# 8860.net
KiCad netlist of a schematic drawn in Altium Designer
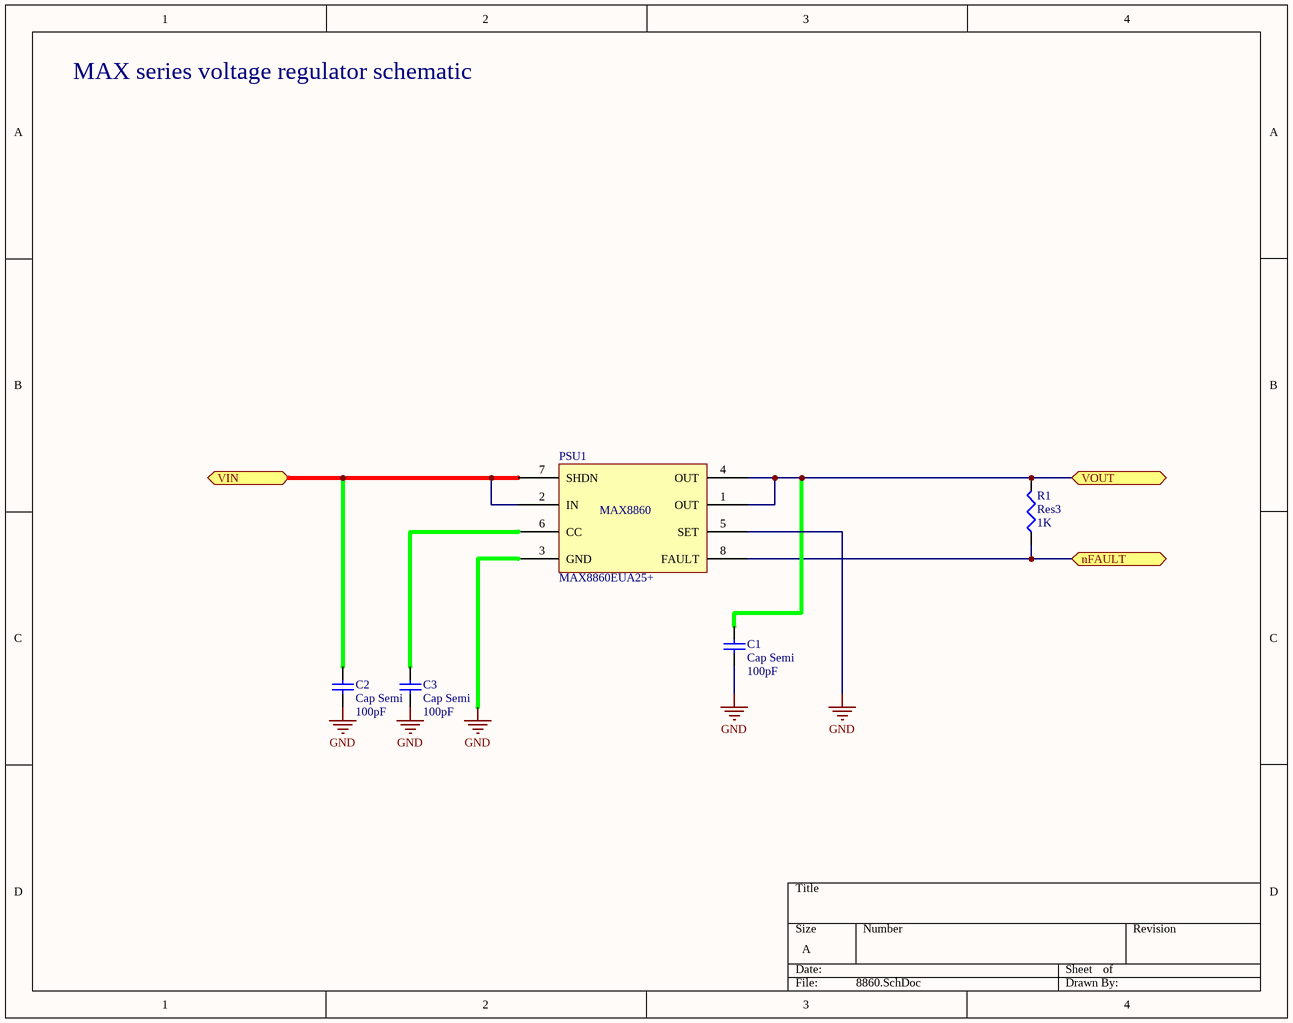
[diagram p0: 8860.SchDoc]

(export (version "E")
  (design (tool "Eeschema 10.0.6"))
  (components
    (comp (ref "C1")
      (value "Cap Semi")
      (footprint "C1206")
      (description "Capacitor (Semiconductor SIM Model)")
      (fields (field (name "ALTIUM_VALUE") "100pF") (field (name "PUBLISHER") "Altium Limited"))
      (libsource (lib "Miscellaneous Devices") (part "Cap Semi"))
    )
    (comp (ref "C2")
      (value "Cap Semi")
      (footprint "C1206")
      (description "Capacitor (Semiconductor SIM Model)")
      (fields (field (name "ALTIUM_VALUE") "100pF") (field (name "PUBLISHER") "Altium Limited"))
      (libsource (lib "Miscellaneous Devices") (part "Cap Semi"))
    )
    (comp (ref "C3")
      (value "Cap Semi")
      (footprint "C1206")
      (description "Capacitor (Semiconductor SIM Model)")
      (fields (field (name "ALTIUM_VALUE") "100pF") (field (name "PUBLISHER") "Altium Limited"))
      (libsource (lib "Miscellaneous Devices") (part "Cap Semi"))
    )
    (comp (ref "PSU1")
      (value "MAX8860EUA25+")
      (footprint "TSOP65P300X110-8N")
      (libsource (lib "ORLY_Lib") (part "MAX8860EUA25+"))
    )
    (comp (ref "R1")
      (value "Res3")
      (footprint "14-1210")
      (description "Resistor")
      (fields (field (name "ALTIUM_VALUE") "1K") (field (name "PUBLISHER") "Altium Limited"))
      (libsource (lib "Miscellaneous Devices") (part "Res3"))
    )
  )
  (nets
    (net (code "1") (name "/VIN") (class "Default")
      (node (ref "C2") (pin "2") (pinfunction "2_2") (pintype "passive"))
      (node (ref "PSU1") (pin "2") (pinfunction "IN_2") (pintype "passive"))
      (node (ref "PSU1") (pin "7") (pinfunction "SHDN_7") (pintype "passive"))
    )
    (net (code "2") (name "/VOUT") (class "Default")
      (node (ref "C1") (pin "2") (pinfunction "2_2") (pintype "passive"))
      (node (ref "PSU1") (pin "1") (pinfunction "OUT_1") (pintype "passive"))
      (node (ref "PSU1") (pin "4") (pinfunction "OUT_4") (pintype "passive"))
      (node (ref "R1") (pin "2") (pinfunction "2_2") (pintype "passive"))
    )
    (net (code "3") (name "/nFAULT") (class "Default")
      (node (ref "PSU1") (pin "8") (pinfunction "FAULT_8") (pintype "passive"))
      (node (ref "R1") (pin "1") (pinfunction "1_1") (pintype "passive"))
    )
    (net (code "4") (name "GND") (class "Default")
      (node (ref "C1") (pin "1") (pinfunction "1_1") (pintype "passive"))
      (node (ref "C2") (pin "1") (pinfunction "1_1") (pintype "passive"))
      (node (ref "C3") (pin "1") (pinfunction "1_1") (pintype "passive"))
      (node (ref "PSU1") (pin "3") (pinfunction "GND_3") (pintype "passive"))
      (node (ref "PSU1") (pin "5") (pinfunction "SET_5") (pintype "passive"))
    )
    (net (code "5") (name "Net-(PSU1-CC)") (class "Default")
      (node (ref "C3") (pin "2") (pinfunction "2_2") (pintype "passive"))
      (node (ref "PSU1") (pin "6") (pinfunction "CC_6") (pintype "passive"))
    )
  )
)
